# WearablesPlatineRFDuino-3.net
KiCad netlist of a schematic drawn in EAGLE
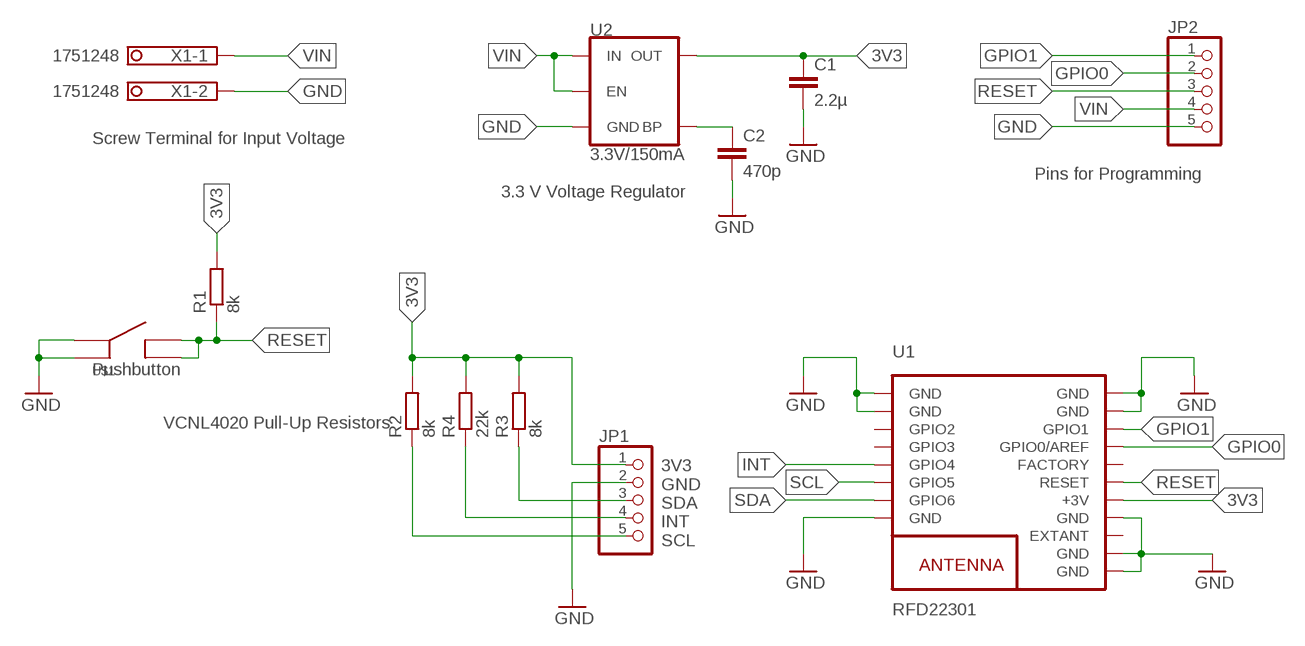
[diagram p0: schematic, sheet 1]

(export (version "E")
  (design (tool "Eeschema 10.0.6"))
  (components
    (comp (ref "C1")
      (value "2.2µ")
      (footprint "eagle-import:C0603")
      (libsource (lib "eagle-import") (part "C-EUC0603"))
    )
    (comp (ref "C2")
      (value "470p")
      (footprint "eagle-import:C0603")
      (libsource (lib "eagle-import") (part "C-EUC0603"))
    )
    (comp (ref "JP1")
      (value "PINHD-1X5")
      (footprint "eagle-import:1X05")
      (libsource (lib "eagle-import") (part "PINHD-1X5"))
    )
    (comp (ref "JP2")
      (value "PINHD-1X5")
      (footprint "eagle-import:1X05")
      (libsource (lib "eagle-import") (part "PINHD-1X5"))
    )
    (comp (ref "R1")
      (value "8k")
      (footprint "eagle-import:R0603")
      (libsource (lib "eagle-import") (part "R-EU_R0603"))
    )
    (comp (ref "R2")
      (value "8k")
      (footprint "eagle-import:R0603")
      (libsource (lib "eagle-import") (part "R-EU_R0603"))
    )
    (comp (ref "R3")
      (value "8k")
      (footprint "eagle-import:R0603")
      (libsource (lib "eagle-import") (part "R-EU_R0603"))
    )
    (comp (ref "R4")
      (value "22k")
      (footprint "eagle-import:R0603")
      (libsource (lib "eagle-import") (part "R-EU_R0603"))
    )
    (comp (ref "U$1")
      (value "TACTILE_SWITCH")
      (footprint "eagle-import:EVQ-PUK02K")
      (libsource (lib "eagle-import") (part "TACTILE_SWITCH"))
    )
    (comp (ref "U1")
      (value "RFD22301")
      (footprint "eagle-import:RFD22301")
      (libsource (lib "eagle-import") (part "RFD22301"))
    )
    (comp (ref "U2")
      (value "3.3V/150mA")
      (footprint "eagle-import:SOT23-5")
      (libsource (lib "eagle-import") (part "V_REG_MIC52053.3V"))
    )
    (comp (ref "X1")
      (value "1751248")
      (footprint "eagle-import:1751248")
      (libsource (lib "eagle-import") (part "1751248"))
    )
  )
  (nets
    (net (code "1") (name "3V3") (class "Default")
      (node (ref "C1") (pin "1") (pinfunction "1_1") (pintype "passive"))
      (node (ref "JP1") (pin "1") (pinfunction "1_1") (pintype "passive"))
      (node (ref "R1") (pin "2") (pinfunction "2_2") (pintype "passive"))
      (node (ref "R2") (pin "2") (pinfunction "2_2") (pintype "passive"))
      (node (ref "R3") (pin "2") (pinfunction "2_2") (pintype "passive"))
      (node (ref "R4") (pin "2") (pinfunction "2_2") (pintype "passive"))
      (node (ref "U1") (pin "13") (pinfunction "+3V_13") (pintype "power_in"))
      (node (ref "U2") (pin "5") (pinfunction "OUT_5") (pintype "passive"))
    )
    (net (code "2") (name "GND") (class "Default")
      (node (ref "C1") (pin "2") (pinfunction "2_2") (pintype "passive"))
      (node (ref "C2") (pin "2") (pinfunction "2_2") (pintype "passive"))
      (node (ref "JP1") (pin "2") (pinfunction "2_2") (pintype "passive"))
      (node (ref "JP2") (pin "5") (pinfunction "5_5") (pintype "passive"))
      (node (ref "U$1") (pin "1") (pinfunction "A_1") (pintype "bidirectional"))
      (node (ref "U$1") (pin "3") (pinfunction "A_3") (pintype "bidirectional"))
      (node (ref "U1") (pin "1") (pinfunction "GND_1") (pintype "power_in"))
      (node (ref "U1") (pin "10") (pinfunction "GND_10") (pintype "power_in"))
      (node (ref "U1") (pin "12") (pinfunction "GND_12") (pintype "power_in"))
      (node (ref "U1") (pin "18") (pinfunction "GND_18") (pintype "power_in"))
      (node (ref "U1") (pin "19") (pinfunction "GND_19") (pintype "power_in"))
      (node (ref "U1") (pin "2") (pinfunction "GND_2") (pintype "power_in"))
      (node (ref "U1") (pin "8") (pinfunction "GND_8") (pintype "power_in"))
      (node (ref "U1") (pin "9") (pinfunction "GND_9") (pintype "power_in"))
      (node (ref "U2") (pin "2") (pinfunction "GND_2") (pintype "input"))
      (node (ref "X1") (pin "2") (pinfunction "K_2") (pintype "passive"))
    )
    (net (code "3") (name "GPIO0") (class "Default")
      (node (ref "JP2") (pin "2") (pinfunction "2_2") (pintype "passive"))
      (node (ref "U1") (pin "16") (pinfunction "GPIO0/AREF_16") (pintype "bidirectional"))
    )
    (net (code "4") (name "GPIO1") (class "Default")
      (node (ref "JP2") (pin "1") (pinfunction "1_1") (pintype "passive"))
      (node (ref "U1") (pin "17") (pinfunction "GPIO1_17") (pintype "bidirectional"))
    )
    (net (code "5") (name "INT") (class "Default")
      (node (ref "JP1") (pin "4") (pinfunction "4_4") (pintype "passive"))
      (node (ref "R4") (pin "1") (pinfunction "1_1") (pintype "passive"))
      (node (ref "U1") (pin "5") (pinfunction "GPIO4_5") (pintype "bidirectional"))
    )
    (net (code "6") (name "Net-(U2-BP)") (class "Default")
      (node (ref "C2") (pin "1") (pinfunction "1_1") (pintype "passive"))
      (node (ref "U2") (pin "4") (pinfunction "BP_4") (pintype "input"))
    )
    (net (code "7") (name "RESET") (class "Default")
      (node (ref "JP2") (pin "3") (pinfunction "3_3") (pintype "passive"))
      (node (ref "R1") (pin "1") (pinfunction "1_1") (pintype "passive"))
      (node (ref "U$1") (pin "2") (pinfunction "B_2") (pintype "bidirectional"))
      (node (ref "U$1") (pin "4") (pinfunction "B_4") (pintype "bidirectional"))
      (node (ref "U1") (pin "14") (pinfunction "RESET_14") (pintype "bidirectional"))
    )
    (net (code "8") (name "SCL") (class "Default")
      (node (ref "JP1") (pin "5") (pinfunction "5_5") (pintype "passive"))
      (node (ref "R2") (pin "1") (pinfunction "1_1") (pintype "passive"))
      (node (ref "U1") (pin "6") (pinfunction "GPIO5_6") (pintype "bidirectional"))
    )
    (net (code "9") (name "SDA") (class "Default")
      (node (ref "JP1") (pin "3") (pinfunction "3_3") (pintype "passive"))
      (node (ref "R3") (pin "1") (pinfunction "1_1") (pintype "passive"))
      (node (ref "U1") (pin "7") (pinfunction "GPIO6_7") (pintype "bidirectional"))
    )
    (net (code "10") (name "VIN") (class "Default")
      (node (ref "JP2") (pin "4") (pinfunction "4_4") (pintype "passive"))
      (node (ref "U2") (pin "1") (pinfunction "IN_1") (pintype "input"))
      (node (ref "U2") (pin "3") (pinfunction "EN_3") (pintype "input"))
      (node (ref "X1") (pin "1") (pinfunction "K_1") (pintype "passive"))
    )
    (net (code "11") (name "unconnected-(U1-EXTANT-Pad11)") (class "Default")
      (node (ref "U1") (pin "11") (pinfunction "EXTANT_11") (pintype "no_connect"))
    )
    (net (code "12") (name "unconnected-(U1-FACTORY-Pad15)") (class "Default")
      (node (ref "U1") (pin "15") (pinfunction "FACTORY_15") (pintype "bidirectional"))
    )
    (net (code "13") (name "unconnected-(U1-GPIO2-Pad3)") (class "Default")
      (node (ref "U1") (pin "3") (pinfunction "GPIO2_3") (pintype "bidirectional"))
    )
    (net (code "14") (name "unconnected-(U1-GPIO3-Pad4)") (class "Default")
      (node (ref "U1") (pin "4") (pinfunction "GPIO3_4") (pintype "bidirectional"))
    )
  )
)
